# LT3080.net
KiCad netlist of a schematic drawn in Altium Designer
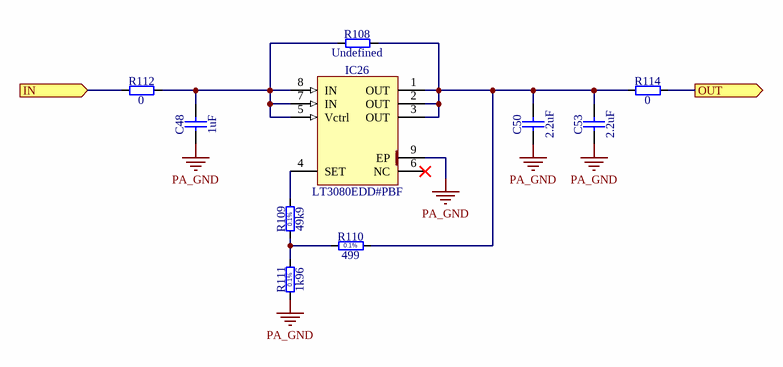
[diagram p0: LT3080.SchDoc]

(export (version "E")
  (design (tool "Eeschema 10.0.6"))
  (components
    (comp (ref "C48")
      (value "1uF")
      (footprint "CAPC1608X87N")
      (description "Non-polarised capacitor")
      (fields
        (field (name "PART NUMBER") "CC0603_1UF_50V_10%_X5R")
        (field (name "VOLTAGE") "50V")
        (field (name "AUTHOR") "CERN DEM JMW")
      )
      (libsource (lib "Capacitors") (part "Capacitor - non polarized"))
    )
    (comp (ref "C50")
      (value "2.2uF")
      (footprint "CAPC2012X140N")
      (description "Non-polarised capacitor")
      (fields
        (field (name "PART NUMBER") "CC0805_2.2UF_50V_10%_X7R")
        (field (name "VOLTAGE") "50V")
        (field (name "AUTHOR") "CERN DEM JLC")
      )
      (libsource (lib "Capacitors") (part "Capacitor - non polarized"))
    )
    (comp (ref "C53")
      (value "2.2uF")
      (footprint "CAPC2012X140N")
      (description "Non-polarised capacitor")
      (fields
        (field (name "PART NUMBER") "CC0805_2.2UF_50V_10%_X7R")
        (field (name "VOLTAGE") "50V")
        (field (name "AUTHOR") "CERN DEM JLC")
      )
      (libsource (lib "Capacitors") (part "Capacitor - non polarized"))
    )
    (comp (ref "IC26")
      (value "LT3080EDD#PBF")
      (footprint "SON50P300X300X80-9N-R175X248")
      (description "Adjustable 1.1A Single Resistor Low Dropout Regulator")
      (fields (field (name "MANUFACTURER") "LINEAR TECHNOLOGY") (field (name "AUTHOR") "CERN DEM JLC"))
      (libsource (lib "ICs And Semiconductors") (part "LT3080EDD"))
    )
    (comp (ref "R108")
      (value "Undefined")
      (footprint "RESC3216X65N")
      (description "Resistor")
      (fields (field (name "PART NUMBER") "R1206_NO-VALUE") (field (name "AUTHOR") "CERN DEM JLC"))
      (libsource (lib "Resistors") (part "Resistor"))
    )
    (comp (ref "R109")
      (value "49k9")
      (footprint "RESC1608X55N")
      (description "Resistor - 0.1%")
      (fields
        (field (name "PART NUMBER") "R0603_49K9_0.1%_0.063W_10PPM")
        (field (name "POWER") "0.063W")
        (field (name "AUTHOR") "CERN DEM JLC")
      )
      (libsource (lib "Resistors") (part "Resistor - 0.1%"))
    )
    (comp (ref "R110")
      (value "499")
      (footprint "RESC1608X55N")
      (description "Resistor - 0.1%")
      (fields
        (field (name "PART NUMBER") "R0603_499R_0.1%_0.063W_10PPM")
        (field (name "POWER") "0.063W")
        (field (name "AUTHOR") "CERN DEM JLC")
      )
      (libsource (lib "Resistors") (part "Resistor - 0.1%"))
    )
    (comp (ref "R111")
      (value "1k96")
      (footprint "RESC1608X55N")
      (description "Resistor - 0.1%")
      (fields
        (field (name "PART NUMBER") "R0603_1K96_0.1%_0.063W_10PPM")
        (field (name "POWER") "0.063W")
        (field (name "AUTHOR") "CERN DEM JLC")
      )
      (libsource (lib "Resistors") (part "Resistor - 0.1%"))
    )
    (comp (ref "R112")
      (value "0")
      (footprint "RESC3216X65N")
      (description "Resistor")
      (fields
        (field (name "PART NUMBER") "R1206_0R_JUMPER")
        (field (name "MANUFACTURER") "GENERIC")
        (field (name "AUTHOR") "CERN DEM JLC")
      )
      (libsource (lib "Resistors") (part "Resistor"))
    )
    (comp (ref "R114")
      (value "0")
      (footprint "RESC3216X65N")
      (description "Resistor")
      (fields
        (field (name "PART NUMBER") "R1206_0R_JUMPER")
        (field (name "MANUFACTURER") "GENERIC")
        (field (name "AUTHOR") "CERN DEM JLC")
      )
      (libsource (lib "Resistors") (part "Resistor"))
    )
  )
  (nets
    (net (code "1") (name "/IN") (class "Default")
      (node (ref "R112") (pin "1") (pinfunction "1_1") (pintype "passive"))
    )
    (net (code "2") (name "/OUT") (class "Default")
      (node (ref "R114") (pin "2") (pinfunction "2_2") (pintype "passive"))
    )
    (net (code "3") (name "Net-(C50-Pad2)") (class "Default")
      (node (ref "C50") (pin "2") (pinfunction "2_2") (pintype "passive"))
      (node (ref "C53") (pin "2") (pinfunction "2_2") (pintype "passive"))
      (node (ref "IC26") (pin "1") (pinfunction "OUT_1") (pintype "power_in"))
      (node (ref "IC26") (pin "2") (pinfunction "OUT_2") (pintype "power_in"))
      (node (ref "IC26") (pin "3") (pinfunction "OUT_3") (pintype "power_in"))
      (node (ref "R108") (pin "2") (pinfunction "2_2") (pintype "passive"))
      (node (ref "R110") (pin "2") (pinfunction "2_2") (pintype "passive"))
      (node (ref "R114") (pin "1") (pinfunction "1_1") (pintype "passive"))
    )
    (net (code "4") (name "Net-(IC26-SET)") (class "Default")
      (node (ref "IC26") (pin "4") (pinfunction "SET_4") (pintype "passive"))
      (node (ref "R109") (pin "2") (pinfunction "2_2") (pintype "passive"))
    )
    (net (code "5") (name "Net-(IC26-Vctrl)") (class "Default")
      (node (ref "C48") (pin "2") (pinfunction "2_2") (pintype "passive"))
      (node (ref "IC26") (pin "5") (pinfunction "Vctrl_5") (pintype "input"))
      (node (ref "IC26") (pin "7") (pinfunction "IN_7") (pintype "input"))
      (node (ref "IC26") (pin "8") (pinfunction "IN_8") (pintype "input"))
      (node (ref "R108") (pin "1") (pinfunction "1_1") (pintype "passive"))
      (node (ref "R112") (pin "2") (pinfunction "2_2") (pintype "passive"))
    )
    (net (code "6") (name "Net-(R109-Pad1)") (class "Default")
      (node (ref "R109") (pin "1") (pinfunction "1_1") (pintype "passive"))
      (node (ref "R110") (pin "1") (pinfunction "1_1") (pintype "passive"))
      (node (ref "R111") (pin "2") (pinfunction "2_2") (pintype "passive"))
    )
    (net (code "7") (name "PA_GND") (class "Default")
      (node (ref "C48") (pin "1") (pinfunction "1_1") (pintype "passive"))
      (node (ref "C50") (pin "1") (pinfunction "1_1") (pintype "passive"))
      (node (ref "C53") (pin "1") (pinfunction "1_1") (pintype "passive"))
      (node (ref "IC26") (pin "9") (pinfunction "EP_9") (pintype "power_in"))
      (node (ref "R111") (pin "1") (pinfunction "1_1") (pintype "passive"))
    )
    (net (code "8") (name "unconnected-(IC26-NC-Pad6)") (class "Default")
      (node (ref "IC26") (pin "6") (pinfunction "NC_6") (pintype "passive+no_connect"))
    )
  )
)
